# stm32g4.net
KiCad netlist of a schematic drawn in Altium Designer
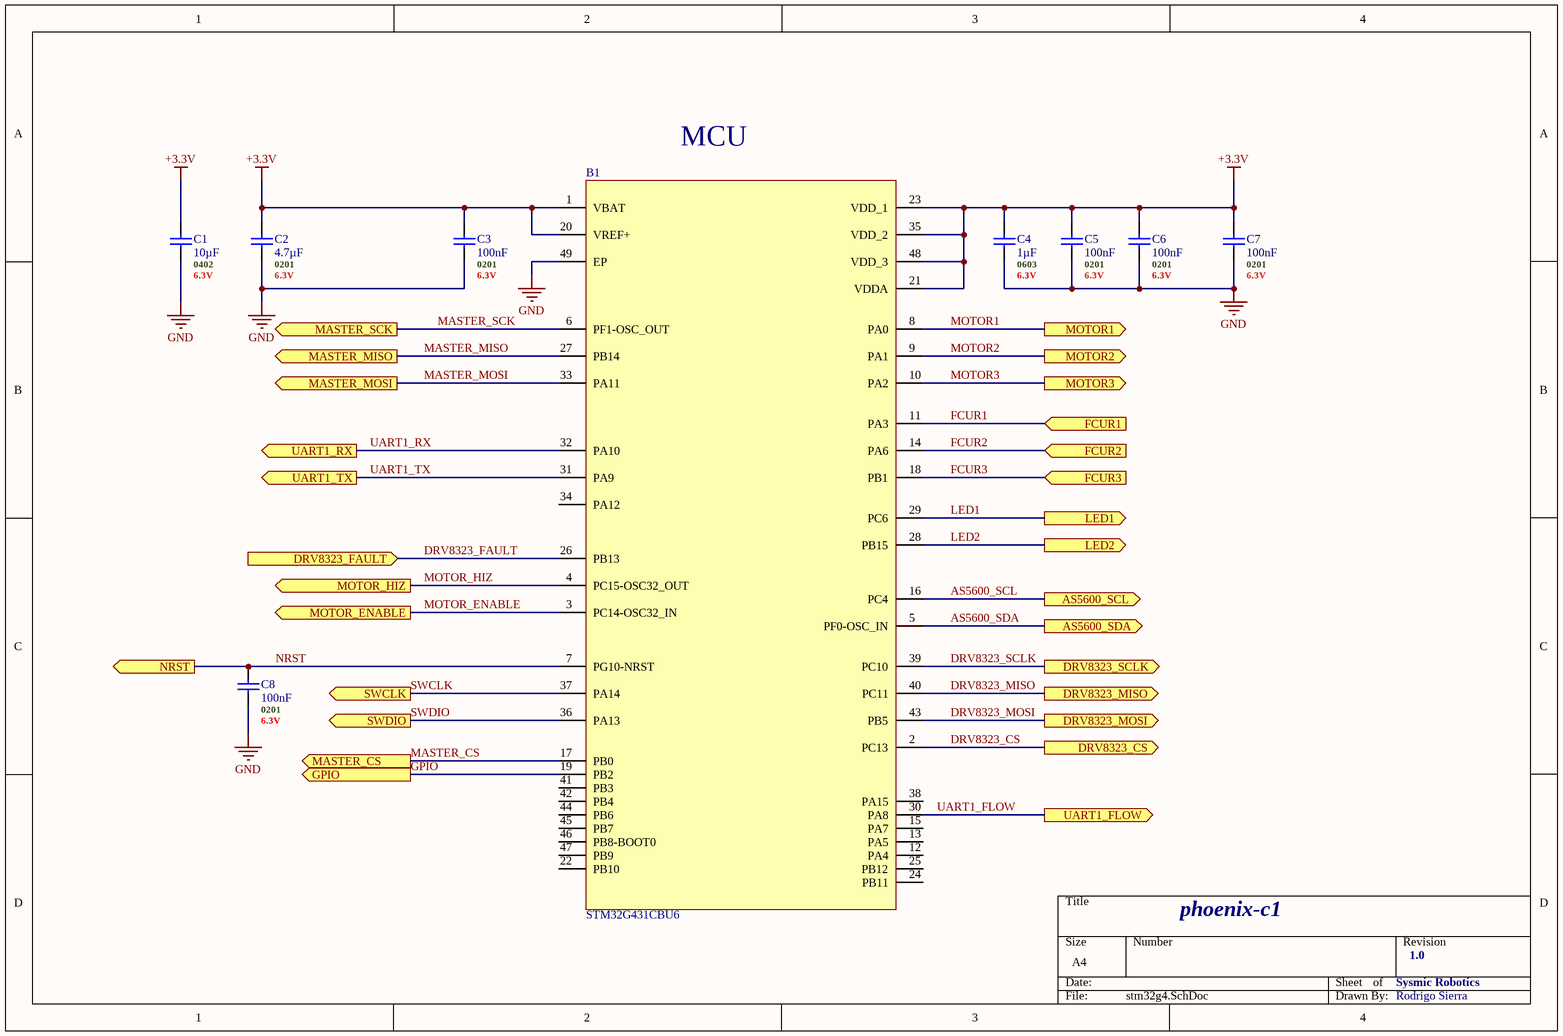
[diagram p0: stm32g4.SchDoc]

(export (version "E")
  (design (tool "Eeschema 10.0.6"))
  (components
    (comp (ref "B1")
      (value "STM32G431CBU6")
      (footprint "48-UFQFN - STMicroelectronics")
      (description "STMICROELECTRONICS - STM32G431CBU6 - MCU, 32BIT, 170MHZ, UFQFPN-48")
      (fields (field (name "MOUSER PART NUMBER") "511-STM32G431CBU6"))
      (libsource (lib "phoenix-c1-schlib") (part "STM32G431CBU6"))
    )
    (comp (ref "C1")
      (value "10µF")
      (footprint "C0402 - MURATA")
      (description "Ceramic Capacitor, Ceramic, 6.3V, 20% +Tol, 20% -Tol, X5R, 15% TC, 10uF, Surface Mount, 0402")
      (fields
        (field (name "MANUFACTURER") "Murata")
        (field (name "MANUFACTURER PART NUMBER") "GRM155R60J106ME05D")
        (field (name ".CASE/PACKAGE") "0402")
        (field (name ".VOLTAGE RATING (DC)") "6.3V")
      )
      (libsource (lib "CAP - GRM155R60J106ME05D") (part "GRM155R60J106ME05D"))
    )
    (comp (ref "C2")
      (value "4.7µF")
      (footprint "C0201 - MURATA")
      (description "Ceramic Capacitor, Ceramic, 6.3V, 20% +Tol, 20% -Tol, X5R, 15% TC, 4.7uF, Surface Mount, 0201")
      (fields
        (field (name "MANUFACTURER") "Murata")
        (field (name "MANUFACTURER PART NUMBER") "GRM035R60J475ME15D")
        (field (name ".CASE/PACKAGE") "0201")
        (field (name ".VOLTAGE RATING (DC)") "6.3V")
      )
      (libsource (lib "CAP - GRM035R60J475ME15D") (part "GRM035R60J475ME15D"))
    )
    (comp (ref "C3")
      (value "100nF")
      (footprint "C0201 - MURATA")
      (fields
        (field (name "MANUFACTURER") "Murata")
        (field (name "MANUFACTURER PART NUMBER") "GRT033R60J104KE01J")
        (field (name "TOLERANCE") "10%")
        (field (name ".CASE/PACKAGE") "0201")
        (field (name ".VOLTAGE RATING (DC)") "6.3V")
      )
      (libsource (lib "CAP - GRT033R60J104KE01J") (part "GRT033R60J104KE01J"))
    )
    (comp (ref "C4")
      (value "1µF")
      (footprint "C0603 - MURATA")
      (description "Ceramic Capacitor, Ceramic, 6.3V, 10% +Tol, 10% -Tol, X5R, 15% TC, 1uF, Surface Mount, 0603")
      (fields
        (field (name "MANUFACTURER") "Murata")
        (field (name "MANUFACTURER PART NUMBER") "GRM188R60J105KA01D")
        (field (name ".CASE/PACKAGE") "0603")
        (field (name ".VOLTAGE RATING (DC)") "6.3V")
      )
      (libsource (lib "CAP - GRM188R60J105KA01D") (part "GRM188R60J105KA01D"))
    )
    (comp (ref "C5")
      (value "100nF")
      (footprint "C0201 - MURATA")
      (fields
        (field (name "MANUFACTURER") "Murata")
        (field (name "MANUFACTURER PART NUMBER") "GRT033R60J104KE01J")
        (field (name "TOLERANCE") "10%")
        (field (name ".CASE/PACKAGE") "0201")
        (field (name ".VOLTAGE RATING (DC)") "6.3V")
      )
      (libsource (lib "CAP - GRT033R60J104KE01J") (part "GRT033R60J104KE01J"))
    )
    (comp (ref "C6")
      (value "100nF")
      (footprint "C0201 - MURATA")
      (fields
        (field (name "MANUFACTURER") "Murata")
        (field (name "MANUFACTURER PART NUMBER") "GRT033R60J104KE01J")
        (field (name "TOLERANCE") "10%")
        (field (name ".CASE/PACKAGE") "0201")
        (field (name ".VOLTAGE RATING (DC)") "6.3V")
      )
      (libsource (lib "CAP - GRT033R60J104KE01J") (part "GRT033R60J104KE01J"))
    )
    (comp (ref "C7")
      (value "100nF")
      (footprint "C0201 - MURATA")
      (fields
        (field (name "MANUFACTURER") "Murata")
        (field (name "MANUFACTURER PART NUMBER") "GRT033R60J104KE01J")
        (field (name "TOLERANCE") "10%")
        (field (name ".CASE/PACKAGE") "0201")
        (field (name ".VOLTAGE RATING (DC)") "6.3V")
      )
      (libsource (lib "CAP - GRT033R60J104KE01J") (part "GRT033R60J104KE01J"))
    )
    (comp (ref "C8")
      (value "100nF")
      (footprint "C0201 - MURATA")
      (fields
        (field (name "MANUFACTURER") "Murata")
        (field (name "MANUFACTURER PART NUMBER") "GRT033R60J104KE01J")
        (field (name "TOLERANCE") "10%")
        (field (name ".CASE/PACKAGE") "0201")
        (field (name ".VOLTAGE RATING (DC)") "6.3V")
      )
      (libsource (lib "CAP - GRT033R60J104KE01J") (part "GRT033R60J104KE01J"))
    )
  )
  (nets
    (net (code "1") (name "+3.3V") (class "Default")
      (node (ref "B1") (pin "1") (pinfunction "VBAT_1") (pintype "power_in"))
      (node (ref "B1") (pin "20") (pinfunction "VREF+_20") (pintype "power_in"))
      (node (ref "B1") (pin "21") (pinfunction "VDDA_21") (pintype "power_in"))
      (node (ref "B1") (pin "23") (pinfunction "VDD_1_23") (pintype "power_in"))
      (node (ref "B1") (pin "35") (pinfunction "VDD_2_35") (pintype "power_in"))
      (node (ref "B1") (pin "48") (pinfunction "VDD_3_48") (pintype "power_in"))
      (node (ref "C1") (pin "2") (pinfunction "2_2") (pintype "passive"))
      (node (ref "C2") (pin "2") (pinfunction "2_2") (pintype "passive"))
      (node (ref "C3") (pin "2") (pinfunction "2_2") (pintype "passive"))
      (node (ref "C4") (pin "2") (pinfunction "2_2") (pintype "passive"))
      (node (ref "C5") (pin "2") (pinfunction "2_2") (pintype "passive"))
      (node (ref "C6") (pin "2") (pinfunction "2_2") (pintype "passive"))
      (node (ref "C7") (pin "2") (pinfunction "2_2") (pintype "passive"))
    )
    (net (code "2") (name "/AS5600_SCL") (class "Default")
      (node (ref "B1") (pin "16") (pinfunction "PC4_16") (pintype "passive"))
    )
    (net (code "3") (name "/AS5600_SDA") (class "Default")
      (node (ref "B1") (pin "5") (pinfunction "PF0-OSC_IN_5") (pintype "passive"))
    )
    (net (code "4") (name "/DRV8323_CS") (class "Default")
      (node (ref "B1") (pin "2") (pinfunction "PC13_2") (pintype "passive"))
    )
    (net (code "5") (name "/DRV8323_FAULT") (class "Default")
      (node (ref "B1") (pin "26") (pinfunction "PB13_26") (pintype "passive"))
    )
    (net (code "6") (name "/DRV8323_MISO") (class "Default")
      (node (ref "B1") (pin "40") (pinfunction "PC11_40") (pintype "passive"))
    )
    (net (code "7") (name "/DRV8323_MOSI") (class "Default")
      (node (ref "B1") (pin "43") (pinfunction "PB5_43") (pintype "passive"))
    )
    (net (code "8") (name "/DRV8323_SCLK") (class "Default")
      (node (ref "B1") (pin "39") (pinfunction "PC10_39") (pintype "passive"))
    )
    (net (code "9") (name "/FCUR1") (class "Default")
      (node (ref "B1") (pin "11") (pinfunction "PA3_11") (pintype "passive"))
    )
    (net (code "10") (name "/FCUR2") (class "Default")
      (node (ref "B1") (pin "14") (pinfunction "PA6_14") (pintype "passive"))
    )
    (net (code "11") (name "/FCUR3") (class "Default")
      (node (ref "B1") (pin "18") (pinfunction "PB1_18") (pintype "passive"))
    )
    (net (code "12") (name "/GPIO") (class "Default")
      (node (ref "B1") (pin "19") (pinfunction "PB2_19") (pintype "passive"))
    )
    (net (code "13") (name "/LED1") (class "Default")
      (node (ref "B1") (pin "29") (pinfunction "PC6_29") (pintype "passive"))
    )
    (net (code "14") (name "/LED2") (class "Default")
      (node (ref "B1") (pin "28") (pinfunction "PB15_28") (pintype "passive"))
    )
    (net (code "15") (name "/MASTER_CS") (class "Default")
      (node (ref "B1") (pin "17") (pinfunction "PB0_17") (pintype "passive"))
    )
    (net (code "16") (name "/MASTER_MISO") (class "Default")
      (node (ref "B1") (pin "27") (pinfunction "PB14_27") (pintype "passive"))
    )
    (net (code "17") (name "/MASTER_MOSI") (class "Default")
      (node (ref "B1") (pin "33") (pinfunction "PA11_33") (pintype "passive"))
    )
    (net (code "18") (name "/MASTER_SCK") (class "Default")
      (node (ref "B1") (pin "6") (pinfunction "PF1-OSC_OUT_6") (pintype "passive"))
    )
    (net (code "19") (name "/MOTOR1") (class "Default")
      (node (ref "B1") (pin "8") (pinfunction "PA0_8") (pintype "passive"))
    )
    (net (code "20") (name "/MOTOR2") (class "Default")
      (node (ref "B1") (pin "9") (pinfunction "PA1_9") (pintype "passive"))
    )
    (net (code "21") (name "/MOTOR3") (class "Default")
      (node (ref "B1") (pin "10") (pinfunction "PA2_10") (pintype "passive"))
    )
    (net (code "22") (name "/MOTOR_ENABLE") (class "Default")
      (node (ref "B1") (pin "3") (pinfunction "PC14-OSC32_IN_3") (pintype "passive"))
    )
    (net (code "23") (name "/MOTOR_HIZ") (class "Default")
      (node (ref "B1") (pin "4") (pinfunction "PC15-OSC32_OUT_4") (pintype "passive"))
    )
    (net (code "24") (name "/NRST") (class "Default")
      (node (ref "B1") (pin "7") (pinfunction "PG10-NRST_7") (pintype "passive"))
      (node (ref "C8") (pin "2") (pinfunction "2_2") (pintype "passive"))
    )
    (net (code "25") (name "/SWCLK") (class "Default")
      (node (ref "B1") (pin "37") (pinfunction "PA14_37") (pintype "passive"))
    )
    (net (code "26") (name "/SWDIO") (class "Default")
      (node (ref "B1") (pin "36") (pinfunction "PA13_36") (pintype "passive"))
    )
    (net (code "27") (name "/UART1_FLOW") (class "Default")
      (node (ref "B1") (pin "30") (pinfunction "PA8_30") (pintype "passive"))
    )
    (net (code "28") (name "/UART1_RX") (class "Default")
      (node (ref "B1") (pin "32") (pinfunction "PA10_32") (pintype "passive"))
    )
    (net (code "29") (name "/UART1_TX") (class "Default")
      (node (ref "B1") (pin "31") (pinfunction "PA9_31") (pintype "passive"))
    )
    (net (code "30") (name "GND") (class "Default")
      (node (ref "B1") (pin "49") (pinfunction "EP_49") (pintype "power_in"))
      (node (ref "C1") (pin "1") (pinfunction "1_1") (pintype "passive"))
      (node (ref "C2") (pin "1") (pinfunction "1_1") (pintype "passive"))
      (node (ref "C3") (pin "1") (pinfunction "1_1") (pintype "passive"))
      (node (ref "C4") (pin "1") (pinfunction "1_1") (pintype "passive"))
      (node (ref "C5") (pin "1") (pinfunction "1_1") (pintype "passive"))
      (node (ref "C6") (pin "1") (pinfunction "1_1") (pintype "passive"))
      (node (ref "C7") (pin "1") (pinfunction "1_1") (pintype "passive"))
      (node (ref "C8") (pin "1") (pinfunction "1_1") (pintype "passive"))
    )
    (net (code "31") (name "unconnected-(B1-PA4-Pad12)") (class "Default")
      (node (ref "B1") (pin "12") (pinfunction "PA4_12") (pintype "passive"))
    )
    (net (code "32") (name "unconnected-(B1-PA5-Pad13)") (class "Default")
      (node (ref "B1") (pin "13") (pinfunction "PA5_13") (pintype "passive"))
    )
    (net (code "33") (name "unconnected-(B1-PA7-Pad15)") (class "Default")
      (node (ref "B1") (pin "15") (pinfunction "PA7_15") (pintype "passive"))
    )
    (net (code "34") (name "unconnected-(B1-PA12-Pad34)") (class "Default")
      (node (ref "B1") (pin "34") (pinfunction "PA12_34") (pintype "passive"))
    )
    (net (code "35") (name "unconnected-(B1-PA15-Pad38)") (class "Default")
      (node (ref "B1") (pin "38") (pinfunction "PA15_38") (pintype "passive"))
    )
    (net (code "36") (name "unconnected-(B1-PB3-Pad41)") (class "Default")
      (node (ref "B1") (pin "41") (pinfunction "PB3_41") (pintype "passive"))
    )
    (net (code "37") (name "unconnected-(B1-PB4-Pad42)") (class "Default")
      (node (ref "B1") (pin "42") (pinfunction "PB4_42") (pintype "passive"))
    )
    (net (code "38") (name "unconnected-(B1-PB6-Pad44)") (class "Default")
      (node (ref "B1") (pin "44") (pinfunction "PB6_44") (pintype "passive"))
    )
    (net (code "39") (name "unconnected-(B1-PB7-Pad45)") (class "Default")
      (node (ref "B1") (pin "45") (pinfunction "PB7_45") (pintype "passive"))
    )
    (net (code "40") (name "unconnected-(B1-PB8-BOOT0-Pad46)") (class "Default")
      (node (ref "B1") (pin "46") (pinfunction "PB8-BOOT0_46") (pintype "passive"))
    )
    (net (code "41") (name "unconnected-(B1-PB9-Pad47)") (class "Default")
      (node (ref "B1") (pin "47") (pinfunction "PB9_47") (pintype "passive"))
    )
    (net (code "42") (name "unconnected-(B1-PB10-Pad22)") (class "Default")
      (node (ref "B1") (pin "22") (pinfunction "PB10_22") (pintype "passive"))
    )
    (net (code "43") (name "unconnected-(B1-PB11-Pad24)") (class "Default")
      (node (ref "B1") (pin "24") (pinfunction "PB11_24") (pintype "passive"))
    )
    (net (code "44") (name "unconnected-(B1-PB12-Pad25)") (class "Default")
      (node (ref "B1") (pin "25") (pinfunction "PB12_25") (pintype "passive"))
    )
  )
)
